# Adafruit_Feather_ESP32-S2.net
KiCad netlist of a schematic drawn in EAGLE
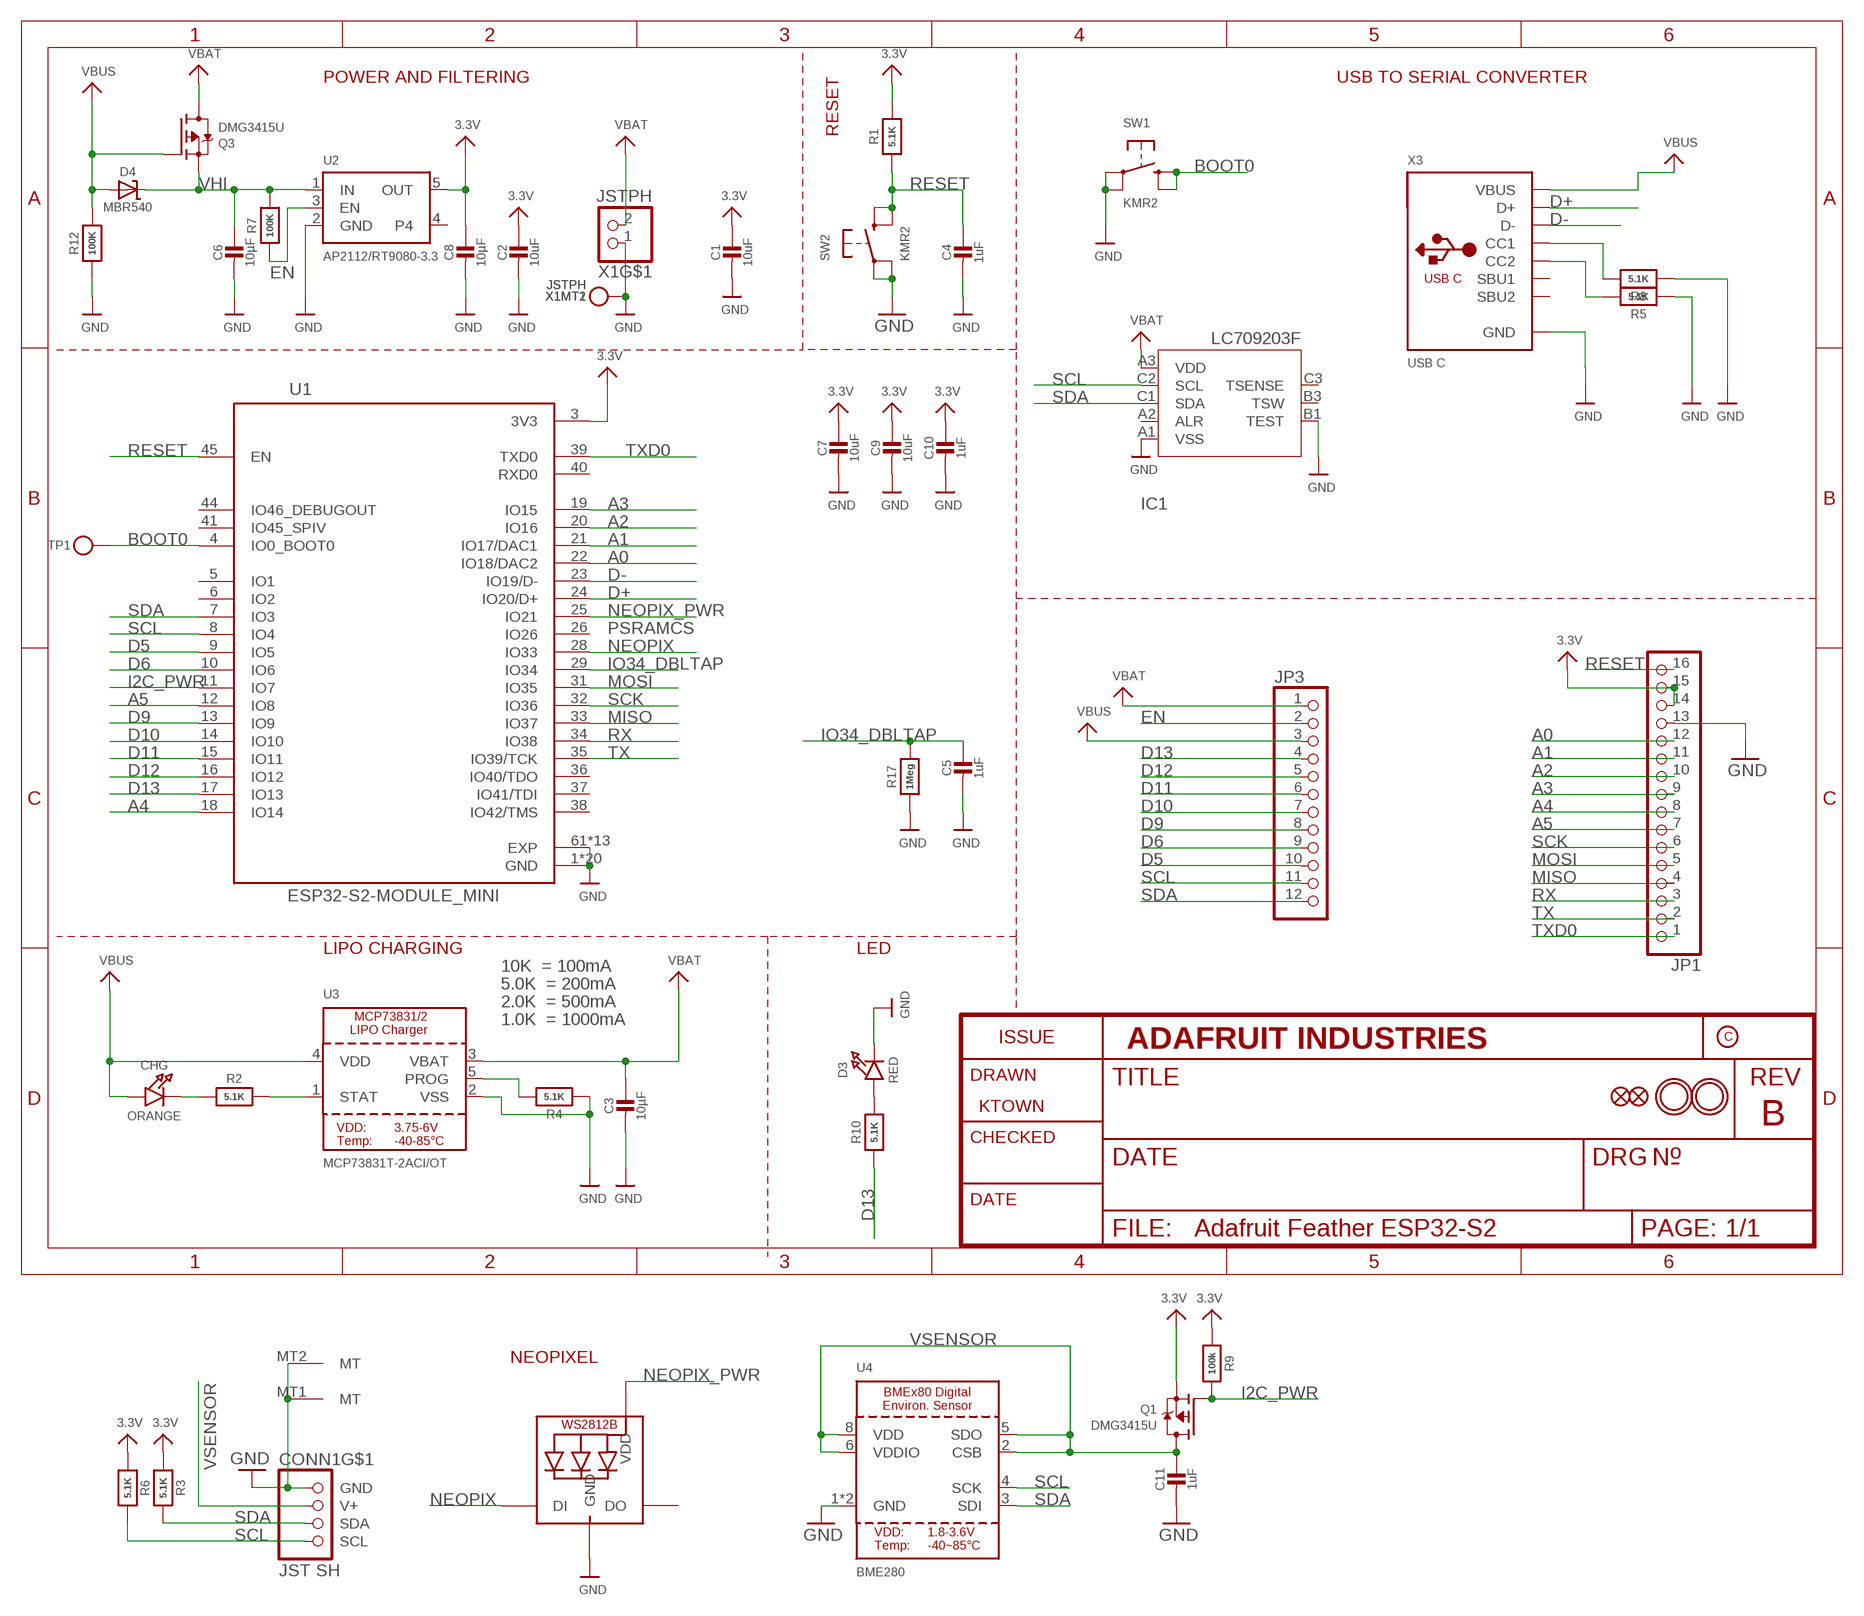
[diagram p0: schematic, sheet 1]

(export (version "E")
  (design (tool "Eeschema 10.0.6"))
  (components
    (comp (ref "C1")
      (value "10uF")
      (footprint "eagle-import:0805-NO")
      (libsource (lib "eagle-import") (part "CAP_CERAMIC0805-NOOUTLINE"))
    )
    (comp (ref "C2")
      (value "10uF")
      (footprint "eagle-import:0805-NO")
      (libsource (lib "eagle-import") (part "CAP_CERAMIC0805-NOOUTLINE"))
    )
    (comp (ref "C3")
      (value "10µF")
      (footprint "eagle-import:0805-NO")
      (libsource (lib "eagle-import") (part "CAP_CERAMIC0805-NOOUTLINE"))
    )
    (comp (ref "C4")
      (value "1uF")
      (footprint "eagle-import:0603-NO")
      (libsource (lib "eagle-import") (part "CAP_CERAMIC0603_NO"))
    )
    (comp (ref "C5")
      (value "1uF")
      (footprint "eagle-import:0603-NO")
      (libsource (lib "eagle-import") (part "CAP_CERAMIC0603_NO"))
    )
    (comp (ref "C6")
      (value "10µF")
      (footprint "eagle-import:0805-NO")
      (libsource (lib "eagle-import") (part "CAP_CERAMIC0805-NOOUTLINE"))
    )
    (comp (ref "C7")
      (value "10uF")
      (footprint "eagle-import:0805-NO")
      (libsource (lib "eagle-import") (part "CAP_CERAMIC0805-NOOUTLINE"))
    )
    (comp (ref "C8")
      (value "10µF")
      (footprint "eagle-import:0805-NO")
      (fields (field (name "REV") "B"))
      (libsource (lib "eagle-import") (part "CAP_CERAMIC0805-NOOUTLINE"))
    )
    (comp (ref "C9")
      (value "10uF")
      (footprint "eagle-import:0805-NO")
      (libsource (lib "eagle-import") (part "CAP_CERAMIC0805-NOOUTLINE"))
    )
    (comp (ref "C10")
      (value "1uF")
      (footprint "eagle-import:0603-NO")
      (libsource (lib "eagle-import") (part "CAP_CERAMIC0603_NO"))
    )
    (comp (ref "C11")
      (value "1uF")
      (footprint "eagle-import:0603-NO")
      (libsource (lib "eagle-import") (part "CAP_CERAMIC0603_NO"))
    )
    (comp (ref "CHG")
      (value "ORANGE")
      (footprint "eagle-import:CHIPLED_0603_NOOUTLINE")
      (libsource (lib "eagle-import") (part "LED0603_NOOUTLINE"))
    )
    (comp (ref "CONN1")
      (value "JST SH")
      (footprint "eagle-import:JST_SH4_RA")
      (libsource (lib "eagle-import") (part "STEMMA_I2C_QTRA"))
    )
    (comp (ref "D3")
      (value "RED")
      (footprint "eagle-import:CHIPLED_0603_NOOUTLINE")
      (libsource (lib "eagle-import") (part "LED0603_NOOUTLINE"))
    )
    (comp (ref "D4")
      (value "MBR540")
      (footprint "eagle-import:SOD-123")
      (libsource (lib "eagle-import") (part "DIODE-SCHOTTKYSOD-123"))
    )
    (comp (ref "IC1")
      (value "LC709203F/MH")
      (footprint "eagle-import:WLCSP9")
      (libsource (lib "eagle-import") (part "LC709203F/MH"))
    )
    (comp (ref "JP1")
      (value "HEADER-1X16ROUND")
      (footprint "eagle-import:1X16_ROUND")
      (libsource (lib "eagle-import") (part "HEADER-1X16ROUND"))
    )
    (comp (ref "JP3")
      (value "HEADER-1X12")
      (footprint "eagle-import:1X12_ROUND")
      (libsource (lib "eagle-import") (part "HEADER-1X12"))
    )
    (comp (ref "LED1")
      (value "WS2812B_SK6805_1515")
      (footprint "eagle-import:SK6805_1515")
      (libsource (lib "eagle-import") (part "WS2812B_SK6805_1515"))
    )
    (comp (ref "Q1")
      (value "DMG3415U")
      (footprint "eagle-import:SOT23-R")
      (libsource (lib "eagle-import") (part "MOSFET-P"))
    )
    (comp (ref "Q3")
      (value "DMG3415U")
      (footprint "eagle-import:SOT23-R")
      (libsource (lib "eagle-import") (part "MOSFET-P"))
    )
    (comp (ref "R1")
      (value "5.1K")
      (footprint "eagle-import:0603-NO")
      (libsource (lib "eagle-import") (part "RESISTOR_0603_NOOUT"))
    )
    (comp (ref "R2")
      (value "5.1K")
      (footprint "eagle-import:0603-NO")
      (libsource (lib "eagle-import") (part "RESISTOR_0603_NOOUT"))
    )
    (comp (ref "R3")
      (value "5.1K")
      (footprint "eagle-import:0603-NO")
      (libsource (lib "eagle-import") (part "RESISTOR_0603_NOOUT"))
    )
    (comp (ref "R4")
      (value "5.1K")
      (footprint "eagle-import:0603-NO")
      (libsource (lib "eagle-import") (part "RESISTOR_0603_NOOUT"))
    )
    (comp (ref "R5")
      (value "5.1K")
      (footprint "eagle-import:0603-NO")
      (libsource (lib "eagle-import") (part "RESISTOR_0603_NOOUT"))
    )
    (comp (ref "R6")
      (value "5.1K")
      (footprint "eagle-import:0603-NO")
      (libsource (lib "eagle-import") (part "RESISTOR_0603_NOOUT"))
    )
    (comp (ref "R7")
      (value "100K")
      (footprint "eagle-import:0603-NO")
      (libsource (lib "eagle-import") (part "RESISTOR_0603_NOOUT"))
    )
    (comp (ref "R8")
      (value "5.1K")
      (footprint "eagle-import:0603-NO")
      (libsource (lib "eagle-import") (part "RESISTOR_0603_NOOUT"))
    )
    (comp (ref "R9")
      (value "100k")
      (footprint "eagle-import:0603-NO")
      (libsource (lib "eagle-import") (part "RESISTOR_0603_NOOUT"))
    )
    (comp (ref "R10")
      (value "5.1K")
      (footprint "eagle-import:0603-NO")
      (libsource (lib "eagle-import") (part "RESISTOR_0603_NOOUT"))
    )
    (comp (ref "R12")
      (value "100K")
      (footprint "eagle-import:0603-NO")
      (libsource (lib "eagle-import") (part "RESISTOR_0603_NOOUT"))
    )
    (comp (ref "R17")
      (value "1Meg")
      (footprint "eagle-import:0603-NO")
      (libsource (lib "eagle-import") (part "RESISTOR_0603_NOOUT"))
    )
    (comp (ref "SW1")
      (value "KMR2")
      (footprint "eagle-import:BTN_KMR2_4.6X2.8")
      (libsource (lib "eagle-import") (part "SWITCH_TACT_SMT4.6X2.8"))
    )
    (comp (ref "SW2")
      (value "KMR2")
      (footprint "eagle-import:BTN_KMR2_4.6X2.8")
      (libsource (lib "eagle-import") (part "SWITCH_TACT_SMT4.6X2.8"))
    )
    (comp (ref "TP1")
      (value "TESTPOINTROUND1.5MMNO")
      (footprint "eagle-import:TESTPOINT_ROUND_1.5MM_NO")
      (libsource (lib "eagle-import") (part "TESTPOINTROUND1.5MMNO"))
    )
    (comp (ref "U$31")
      (value "MOUNTINGHOLE2.5")
      (footprint "eagle-import:MOUNTINGHOLE_2.5_PLATED")
      (libsource (lib "eagle-import") (part "MOUNTINGHOLE2.5"))
    )
    (comp (ref "U$32")
      (value "MOUNTINGHOLE2.5")
      (footprint "eagle-import:MOUNTINGHOLE_2.5_PLATED")
      (libsource (lib "eagle-import") (part "MOUNTINGHOLE2.5"))
    )
    (comp (ref "U$34")
      (value "FIDUCIAL_1MM")
      (footprint "eagle-import:FIDUCIAL_1MM")
      (libsource (lib "eagle-import") (part "FIDUCIAL_1MM"))
    )
    (comp (ref "U$35")
      (value "FIDUCIAL_1MM")
      (footprint "eagle-import:FIDUCIAL_1MM")
      (libsource (lib "eagle-import") (part "FIDUCIAL_1MM"))
    )
    (comp (ref "U1")
      (value "ESP32-S2-MODULE_MINI")
      (footprint "eagle-import:QFN60_ESP32-S2-MINI-1_EXP")
      (libsource (lib "eagle-import") (part "ESP32-S2-MODULE_MINI"))
    )
    (comp (ref "U2")
      (value "AP2112/RT9080-3.3")
      (footprint "eagle-import:SOT23-5")
      (libsource (lib "eagle-import") (part "VREG_SOT23-5"))
    )
    (comp (ref "U3")
      (value "MCP73831T-2ACI/OT")
      (footprint "eagle-import:SOT23-5")
      (libsource (lib "eagle-import") (part "MCP73831/2"))
    )
    (comp (ref "U4")
      (value "BME280")
      (footprint "eagle-import:BME280")
      (libsource (lib "eagle-import") (part "BME280"))
    )
    (comp (ref "X1")
      (value "JSTPH")
      (footprint "eagle-import:JSTPH2_BATT")
      (libsource (lib "eagle-import") (part "CON_JST_PH_2PIN_MT_BATT"))
    )
    (comp (ref "X3")
      (value "USB C")
      (footprint "eagle-import:USB_C_CUSB31-CFM2AX-01-X")
      (libsource (lib "eagle-import") (part "USB_C"))
    )
  )
  (nets
    (net (code "1") (name "/A0") (class "Default")
      (node (ref "JP1") (pin "12") (pinfunction "12_12") (pintype "passive"))
      (node (ref "U1") (pin "22") (pinfunction "IO18/DAC2_22") (pintype "bidirectional"))
    )
    (net (code "2") (name "/A1") (class "Default")
      (node (ref "JP1") (pin "11") (pinfunction "11_11") (pintype "passive"))
      (node (ref "U1") (pin "21") (pinfunction "IO17/DAC1_21") (pintype "bidirectional"))
    )
    (net (code "3") (name "/A2") (class "Default")
      (node (ref "JP1") (pin "10") (pinfunction "10_10") (pintype "passive"))
      (node (ref "U1") (pin "20") (pinfunction "IO16_20") (pintype "bidirectional"))
    )
    (net (code "4") (name "/A3") (class "Default")
      (node (ref "JP1") (pin "9") (pinfunction "9_9") (pintype "passive"))
      (node (ref "U1") (pin "19") (pinfunction "IO15_19") (pintype "bidirectional"))
    )
    (net (code "5") (name "/A4") (class "Default")
      (node (ref "JP1") (pin "8") (pinfunction "8_8") (pintype "passive"))
      (node (ref "U1") (pin "18") (pinfunction "IO14_18") (pintype "bidirectional"))
    )
    (net (code "6") (name "/A5") (class "Default")
      (node (ref "JP1") (pin "7") (pinfunction "7_7") (pintype "passive"))
      (node (ref "U1") (pin "12") (pinfunction "IO8_12") (pintype "bidirectional"))
    )
    (net (code "7") (name "/BOOT0") (class "Default")
      (node (ref "SW1") (pin "B") (pinfunction "S_B") (pintype "passive"))
      (node (ref "SW1") (pin "B'") (pinfunction "S1_B'") (pintype "passive"))
      (node (ref "TP1") (pin "P$1") (pinfunction "P$1_P$1") (pintype "bidirectional"))
      (node (ref "U1") (pin "4") (pinfunction "IO0_BOOT0_4") (pintype "bidirectional"))
    )
    (net (code "8") (name "/D+") (class "Default")
      (node (ref "U1") (pin "24") (pinfunction "IO20/D+_24") (pintype "bidirectional"))
      (node (ref "X3") (pin "A6") (pinfunction "D+_A6") (pintype "bidirectional"))
      (node (ref "X3") (pin "B6") (pinfunction "D+_B6") (pintype "bidirectional"))
    )
    (net (code "9") (name "/D-") (class "Default")
      (node (ref "U1") (pin "23") (pinfunction "IO19/D-_23") (pintype "bidirectional"))
      (node (ref "X3") (pin "A7") (pinfunction "D-_A7") (pintype "bidirectional"))
      (node (ref "X3") (pin "B7") (pinfunction "D-_B7") (pintype "bidirectional"))
    )
    (net (code "10") (name "/D5") (class "Default")
      (node (ref "JP3") (pin "10") (pinfunction "10_10") (pintype "passive"))
      (node (ref "U1") (pin "9") (pinfunction "IO5_9") (pintype "bidirectional"))
    )
    (net (code "11") (name "/D6") (class "Default")
      (node (ref "JP3") (pin "9") (pinfunction "9_9") (pintype "passive"))
      (node (ref "U1") (pin "10") (pinfunction "IO6_10") (pintype "bidirectional"))
    )
    (net (code "12") (name "/D9") (class "Default")
      (node (ref "JP3") (pin "8") (pinfunction "8_8") (pintype "passive"))
      (node (ref "U1") (pin "13") (pinfunction "IO9_13") (pintype "bidirectional"))
    )
    (net (code "13") (name "/D10") (class "Default")
      (node (ref "JP3") (pin "7") (pinfunction "7_7") (pintype "passive"))
      (node (ref "U1") (pin "14") (pinfunction "IO10_14") (pintype "bidirectional"))
    )
    (net (code "14") (name "/D11") (class "Default")
      (node (ref "JP3") (pin "6") (pinfunction "6_6") (pintype "passive"))
      (node (ref "U1") (pin "15") (pinfunction "IO11_15") (pintype "bidirectional"))
    )
    (net (code "15") (name "/D12") (class "Default")
      (node (ref "JP3") (pin "5") (pinfunction "5_5") (pintype "passive"))
      (node (ref "U1") (pin "16") (pinfunction "IO12_16") (pintype "bidirectional"))
    )
    (net (code "16") (name "/D13") (class "Default")
      (node (ref "JP3") (pin "4") (pinfunction "4_4") (pintype "passive"))
      (node (ref "R10") (pin "1") (pinfunction "1_1") (pintype "passive"))
      (node (ref "U1") (pin "17") (pinfunction "IO13_17") (pintype "bidirectional"))
    )
    (net (code "17") (name "/EN") (class "Default")
      (node (ref "JP3") (pin "2") (pinfunction "2_2") (pintype "passive"))
      (node (ref "R7") (pin "1") (pinfunction "1_1") (pintype "passive"))
      (node (ref "U2") (pin "3") (pinfunction "EN_3") (pintype "input"))
    )
    (net (code "18") (name "/I2C_PWR") (class "Default")
      (node (ref "Q1") (pin "1") (pinfunction "G_1") (pintype "passive"))
      (node (ref "R9") (pin "1") (pinfunction "1_1") (pintype "passive"))
      (node (ref "U1") (pin "11") (pinfunction "IO7_11") (pintype "bidirectional"))
    )
    (net (code "19") (name "/IO34_DBLTAP") (class "Default")
      (node (ref "C5") (pin "1") (pinfunction "1_1") (pintype "passive"))
      (node (ref "R17") (pin "2") (pinfunction "2_2") (pintype "passive"))
      (node (ref "U1") (pin "29") (pinfunction "IO34_29") (pintype "input"))
    )
    (net (code "20") (name "/MISO") (class "Default")
      (node (ref "JP1") (pin "4") (pinfunction "4_4") (pintype "passive"))
      (node (ref "U1") (pin "33") (pinfunction "IO37_33") (pintype "bidirectional"))
    )
    (net (code "21") (name "/MOSI") (class "Default")
      (node (ref "JP1") (pin "5") (pinfunction "5_5") (pintype "passive"))
      (node (ref "U1") (pin "31") (pinfunction "IO35_31") (pintype "input"))
    )
    (net (code "22") (name "/NEOPIX") (class "Default")
      (node (ref "LED1") (pin "1") (pinfunction "DI_1") (pintype "input"))
      (node (ref "U1") (pin "28") (pinfunction "IO33_28") (pintype "bidirectional"))
    )
    (net (code "23") (name "/NEOPIX_PWR") (class "Default")
      (node (ref "LED1") (pin "2") (pinfunction "VDD_2") (pintype "power_in"))
      (node (ref "U1") (pin "25") (pinfunction "IO21_25") (pintype "bidirectional"))
    )
    (net (code "24") (name "/RESET") (class "Default")
      (node (ref "C4") (pin "1") (pinfunction "1_1") (pintype "passive"))
      (node (ref "JP1") (pin "16") (pinfunction "16_16") (pintype "passive"))
      (node (ref "R1") (pin "1") (pinfunction "1_1") (pintype "passive"))
      (node (ref "SW2") (pin "B") (pinfunction "S_B") (pintype "passive"))
      (node (ref "SW2") (pin "B'") (pinfunction "S1_B'") (pintype "passive"))
      (node (ref "U1") (pin "45") (pinfunction "EN_45") (pintype "input"))
    )
    (net (code "25") (name "/RX") (class "Default")
      (node (ref "JP1") (pin "3") (pinfunction "3_3") (pintype "passive"))
      (node (ref "U1") (pin "34") (pinfunction "IO38_34") (pintype "bidirectional"))
    )
    (net (code "26") (name "/SCK") (class "Default")
      (node (ref "JP1") (pin "6") (pinfunction "6_6") (pintype "passive"))
      (node (ref "U1") (pin "32") (pinfunction "IO36_32") (pintype "bidirectional"))
    )
    (net (code "27") (name "/SCL") (class "Default")
      (node (ref "CONN1") (pin "4") (pinfunction "SCL_4") (pintype "passive"))
      (node (ref "IC1") (pin "C2") (pinfunction "SCL_C2") (pintype "bidirectional"))
      (node (ref "JP3") (pin "11") (pinfunction "11_11") (pintype "passive"))
      (node (ref "R6") (pin "2") (pinfunction "2_2") (pintype "passive"))
      (node (ref "U1") (pin "8") (pinfunction "IO4_8") (pintype "bidirectional"))
      (node (ref "U4") (pin "4") (pinfunction "SCK_4") (pintype "input"))
    )
    (net (code "28") (name "/SDA") (class "Default")
      (node (ref "CONN1") (pin "3") (pinfunction "SDA_3") (pintype "passive"))
      (node (ref "IC1") (pin "C1") (pinfunction "SDA_C1") (pintype "bidirectional"))
      (node (ref "JP3") (pin "12") (pinfunction "12_12") (pintype "passive"))
      (node (ref "R3") (pin "2") (pinfunction "2_2") (pintype "passive"))
      (node (ref "U1") (pin "7") (pinfunction "IO3_7") (pintype "bidirectional"))
      (node (ref "U4") (pin "3") (pinfunction "SDI_3") (pintype "input"))
    )
    (net (code "29") (name "/TX") (class "Default")
      (node (ref "JP1") (pin "2") (pinfunction "2_2") (pintype "passive"))
      (node (ref "U1") (pin "35") (pinfunction "IO39/TCK_35") (pintype "bidirectional"))
    )
    (net (code "30") (name "/TXD0") (class "Default")
      (node (ref "JP1") (pin "1") (pinfunction "1_1") (pintype "passive"))
      (node (ref "U1") (pin "39") (pinfunction "TXD0_39") (pintype "bidirectional"))
    )
    (net (code "31") (name "/VHI") (class "Default")
      (node (ref "C6") (pin "1") (pinfunction "1_1") (pintype "passive"))
      (node (ref "D4") (pin "C") (pinfunction "C_C") (pintype "passive"))
      (node (ref "Q3") (pin "2") (pinfunction "S_2") (pintype "passive"))
      (node (ref "R7") (pin "2") (pinfunction "2_2") (pintype "passive"))
      (node (ref "U2") (pin "1") (pinfunction "IN_1") (pintype "power_in"))
    )
    (net (code "32") (name "/VSENSOR") (class "Default")
      (node (ref "C11") (pin "1") (pinfunction "1_1") (pintype "passive"))
      (node (ref "CONN1") (pin "2") (pinfunction "V+_2") (pintype "passive"))
      (node (ref "Q1") (pin "3") (pinfunction "D_3") (pintype "passive"))
      (node (ref "U4") (pin "2") (pinfunction "CSB_2") (pintype "input"))
      (node (ref "U4") (pin "5") (pinfunction "SDO_5") (pintype "output"))
      (node (ref "U4") (pin "6") (pinfunction "VDDIO_6") (pintype "power_in"))
      (node (ref "U4") (pin "8") (pinfunction "VDD_8") (pintype "power_in"))
    )
    (net (code "33") (name "3.3V") (class "Default")
      (node (ref "C1") (pin "1") (pinfunction "1_1") (pintype "passive"))
      (node (ref "C10") (pin "1") (pinfunction "1_1") (pintype "passive"))
      (node (ref "C2") (pin "1") (pinfunction "1_1") (pintype "passive"))
      (node (ref "C7") (pin "1") (pinfunction "1_1") (pintype "passive"))
      (node (ref "C8") (pin "1") (pinfunction "1_1") (pintype "passive"))
      (node (ref "C9") (pin "1") (pinfunction "1_1") (pintype "passive"))
      (node (ref "JP1") (pin "14") (pinfunction "14_14") (pintype "passive"))
      (node (ref "JP1") (pin "15") (pinfunction "15_15") (pintype "passive"))
      (node (ref "Q1") (pin "2") (pinfunction "S_2") (pintype "passive"))
      (node (ref "R1") (pin "2") (pinfunction "2_2") (pintype "passive"))
      (node (ref "R3") (pin "1") (pinfunction "1_1") (pintype "passive"))
      (node (ref "R6") (pin "1") (pinfunction "1_1") (pintype "passive"))
      (node (ref "R9") (pin "2") (pinfunction "2_2") (pintype "passive"))
      (node (ref "U1") (pin "3") (pinfunction "3V3_3") (pintype "power_in"))
      (node (ref "U2") (pin "5") (pinfunction "OUT_5") (pintype "power_in"))
    )
    (net (code "34") (name "GND") (class "Default")
      (node (ref "C1") (pin "2") (pinfunction "2_2") (pintype "passive"))
      (node (ref "C10") (pin "2") (pinfunction "2_2") (pintype "passive"))
      (node (ref "C11") (pin "2") (pinfunction "2_2") (pintype "passive"))
      (node (ref "C2") (pin "2") (pinfunction "2_2") (pintype "passive"))
      (node (ref "C3") (pin "2") (pinfunction "2_2") (pintype "passive"))
      (node (ref "C4") (pin "2") (pinfunction "2_2") (pintype "passive"))
      (node (ref "C5") (pin "2") (pinfunction "2_2") (pintype "passive"))
      (node (ref "C6") (pin "2") (pinfunction "2_2") (pintype "passive"))
      (node (ref "C7") (pin "2") (pinfunction "2_2") (pintype "passive"))
      (node (ref "C8") (pin "2") (pinfunction "2_2") (pintype "passive"))
      (node (ref "C9") (pin "2") (pinfunction "2_2") (pintype "passive"))
      (node (ref "CONN1") (pin "1") (pinfunction "GND_1") (pintype "passive"))
      (node (ref "CONN1") (pin "MT1") (pinfunction "MT_MT1") (pintype "bidirectional"))
      (node (ref "CONN1") (pin "MT2") (pinfunction "MT_MT2") (pintype "bidirectional"))
      (node (ref "D3") (pin "C") (pinfunction "C_C") (pintype "passive"))
      (node (ref "IC1") (pin "A1") (pinfunction "VSS_A1") (pintype "power_in"))
      (node (ref "IC1") (pin "B1") (pinfunction "TEST_B1") (pintype "input"))
      (node (ref "JP1") (pin "13") (pinfunction "13_13") (pintype "passive"))
      (node (ref "LED1") (pin "4") (pinfunction "GND_4") (pintype "power_in"))
      (node (ref "R12") (pin "1") (pinfunction "1_1") (pintype "passive"))
      (node (ref "R17") (pin "1") (pinfunction "1_1") (pintype "passive"))
      (node (ref "R4") (pin "1") (pinfunction "1_1") (pintype "passive"))
      (node (ref "R5") (pin "1") (pinfunction "1_1") (pintype "passive"))
      (node (ref "R8") (pin "1") (pinfunction "1_1") (pintype "passive"))
      (node (ref "SW1") (pin "A") (pinfunction "P_A") (pintype "passive"))
      (node (ref "SW1") (pin "A'") (pinfunction "P1_A'") (pintype "passive"))
      (node (ref "SW2") (pin "A") (pinfunction "P_A") (pintype "passive"))
      (node (ref "SW2") (pin "A'") (pinfunction "P1_A'") (pintype "passive"))
      (node (ref "U1") (pin "1") (pinfunction "GND_1") (pintype "power_in"))
      (node (ref "U1") (pin "2") (pinfunction "GND_2") (pintype "power_in"))
      (node (ref "U1") (pin "30") (pinfunction "GND_30") (pintype "power_in"))
      (node (ref "U1") (pin "42") (pinfunction "GND_42") (pintype "power_in"))
      (node (ref "U1") (pin "43") (pinfunction "GND_43") (pintype "power_in"))
      (node (ref "U1") (pin "46") (pinfunction "GND_46") (pintype "power_in"))
      (node (ref "U1") (pin "47") (pinfunction "GND_47") (pintype "power_in"))
      (node (ref "U1") (pin "48") (pinfunction "GND_48") (pintype "power_in"))
      (node (ref "U1") (pin "49") (pinfunction "GND_49") (pintype "power_in"))
      (node (ref "U1") (pin "50") (pinfunction "GND_50") (pintype "power_in"))
      (node (ref "U1") (pin "51") (pinfunction "GND_51") (pintype "power_in"))
      (node (ref "U1") (pin "52") (pinfunction "GND_52") (pintype "power_in"))
      (node (ref "U1") (pin "53") (pinfunction "GND_53") (pintype "power_in"))
      (node (ref "U1") (pin "54") (pinfunction "GND_54") (pintype "power_in"))
      (node (ref "U1") (pin "55") (pinfunction "GND_55") (pintype "power_in"))
      (node (ref "U1") (pin "56") (pinfunction "GND_56") (pintype "power_in"))
      (node (ref "U1") (pin "57") (pinfunction "GND_57") (pintype "power_in"))
      (node (ref "U1") (pin "58") (pinfunction "GND_58") (pintype "power_in"))
      (node (ref "U1") (pin "59") (pinfunction "GND_59") (pintype "power_in"))
      (node (ref "U1") (pin "60") (pinfunction "GND_60") (pintype "power_in"))
      (node (ref "U1") (pin "61") (pinfunction "EXP_61") (pintype "power_in"))
      (node (ref "U1") (pin "62") (pinfunction "EXP_62") (pintype "power_in"))
      (node (ref "U1") (pin "63") (pinfunction "EXP_63") (pintype "power_in"))
      (node (ref "U1") (pin "64") (pinfunction "EXP_64") (pintype "power_in"))
      (node (ref "U1") (pin "65") (pinfunction "EXP_65") (pintype "power_in"))
      (node (ref "U1") (pin "66") (pinfunction "EXP_66") (pintype "power_in"))
      (node (ref "U1") (pin "67") (pinfunction "EXP_67") (pintype "power_in"))
      (node (ref "U1") (pin "68") (pinfunction "EXP_68") (pintype "power_in"))
      (node (ref "U1") (pin "69") (pinfunction "EXP_69") (pintype "power_in"))
      (node (ref "U1") (pin "70") (pinfunction "EXP_70") (pintype "power_in"))
      (node (ref "U1") (pin "71") (pinfunction "EXP_71") (pintype "power_in"))
      (node (ref "U1") (pin "72") (pinfunction "EXP_72") (pintype "power_in"))
      (node (ref "U1") (pin "73") (pinfunction "EXP_73") (pintype "power_in"))
      (node (ref "U2") (pin "2") (pinfunction "GND_2") (pintype "power_in"))
      (node (ref "U3") (pin "2") (pinfunction "VSS_2") (pintype "power_in"))
      (node (ref "U4") (pin "1") (pinfunction "GND_1") (pintype "power_in"))
      (node (ref "U4") (pin "7") (pinfunction "GND_7") (pintype "power_in"))
      (node (ref "X1") (pin "1") (pinfunction "1_1") (pintype "passive"))
      (node (ref "X1") (pin "NC1") (pinfunction "P$1_NC1") (pintype "bidirectional"))
      (node (ref "X1") (pin "NC2") (pinfunction "P$1_NC2") (pintype "bidirectional"))
      (node (ref "X3") (pin "A1B12") (pinfunction "GND_A1B12") (pintype "power_in"))
      (node (ref "X3") (pin "B1A12") (pinfunction "GND_B1A12") (pintype "power_in"))
    )
    (net (code "35") (name "Net-(CHG-PadC)") (class "Default")
      (node (ref "CHG") (pin "C") (pinfunction "C_C") (pintype "passive"))
      (node (ref "R2") (pin "1") (pinfunction "1_1") (pintype "passive"))
    )
    (net (code "36") (name "Net-(D3-PadA)") (class "Default")
      (node (ref "D3") (pin "A") (pinfunction "A_A") (pintype "passive"))
      (node (ref "R10") (pin "2") (pinfunction "2_2") (pintype "passive"))
    )
    (net (code "37") (name "Net-(U3-PROG)") (class "Default")
      (node (ref "R4") (pin "2") (pinfunction "2_2") (pintype "passive"))
      (node (ref "U3") (pin "5") (pinfunction "PROG_5") (pintype "input"))
    )
    (net (code "38") (name "Net-(U3-STAT)") (class "Default")
      (node (ref "R2") (pin "2") (pinfunction "2_2") (pintype "passive"))
      (node (ref "U3") (pin "1") (pinfunction "STAT_1") (pintype "output"))
    )
    (net (code "39") (name "Net-(X3-CC1)") (class "Default")
      (node (ref "R8") (pin "2") (pinfunction "2_2") (pintype "passive"))
      (node (ref "X3") (pin "A5") (pinfunction "CC1_A5") (pintype "bidirectional"))
    )
    (net (code "40") (name "Net-(X3-CC2)") (class "Default")
      (node (ref "R5") (pin "2") (pinfunction "2_2") (pintype "passive"))
      (node (ref "X3") (pin "B5") (pinfunction "CC2_B5") (pintype "bidirectional"))
    )
    (net (code "41") (name "VBAT") (class "Default")
      (node (ref "C3") (pin "1") (pinfunction "1_1") (pintype "passive"))
      (node (ref "IC1") (pin "A3") (pinfunction "VDD_A3") (pintype "power_in"))
      (node (ref "JP3") (pin "1") (pinfunction "1_1") (pintype "passive"))
      (node (ref "Q3") (pin "3") (pinfunction "D_3") (pintype "passive"))
      (node (ref "U3") (pin "3") (pinfunction "VBAT_3") (pintype "power_in"))
      (node (ref "X1") (pin "2") (pinfunction "2_2") (pintype "passive"))
    )
    (net (code "42") (name "VBUS") (class "Default")
      (node (ref "CHG") (pin "A") (pinfunction "A_A") (pintype "passive"))
      (node (ref "D4") (pin "A") (pinfunction "A_A") (pintype "passive"))
      (node (ref "JP3") (pin "3") (pinfunction "3_3") (pintype "passive"))
      (node (ref "Q3") (pin "1") (pinfunction "G_1") (pintype "passive"))
      (node (ref "R12") (pin "2") (pinfunction "2_2") (pintype "passive"))
      (node (ref "U3") (pin "4") (pinfunction "VDD_4") (pintype "power_in"))
      (node (ref "X3") (pin "A4B9") (pinfunction "VBUS_A4B9") (pintype "power_in"))
      (node (ref "X3") (pin "B4A9") (pinfunction "VBUS_B4A9") (pintype "power_in"))
    )
    (net (code "43") (name "unconnected-(IC1-ALR-PadA2)") (class "Default")
      (node (ref "IC1") (pin "A2") (pinfunction "ALR_A2") (pintype "output"))
    )
    (net (code "44") (name "unconnected-(IC1-TSENSE-PadC3)") (class "Default")
      (node (ref "IC1") (pin "C3") (pinfunction "TSENSE_C3") (pintype "passive"))
    )
    (net (code "45") (name "unconnected-(IC1-TSW-PadB3)") (class "Default")
      (node (ref "IC1") (pin "B3") (pinfunction "TSW_B3") (pintype "output"))
    )
    (net (code "46") (name "unconnected-(LED1-DO-Pad3)") (class "Default")
      (node (ref "LED1") (pin "3") (pinfunction "DO_3") (pintype "output"))
    )
    (net (code "47") (name "unconnected-(U1-IO1-Pad5)") (class "Default")
      (node (ref "U1") (pin "5") (pinfunction "IO1_5") (pintype "bidirectional"))
    )
    (net (code "48") (name "unconnected-(U1-IO2-Pad6)") (class "Default")
      (node (ref "U1") (pin "6") (pinfunction "IO2_6") (pintype "bidirectional"))
    )
    (net (code "49") (name "unconnected-(U1-IO26-Pad26)") (class "Default")
      (node (ref "U1") (pin "26") (pinfunction "IO26_26") (pintype "bidirectional"))
    )
    (net (code "50") (name "unconnected-(U1-IO40{slash}TDO-Pad36)") (class "Default")
      (node (ref "U1") (pin "36") (pinfunction "IO40/TDO_36") (pintype "bidirectional"))
    )
    (net (code "51") (name "unconnected-(U1-IO41{slash}TDI-Pad37)") (class "Default")
      (node (ref "U1") (pin "37") (pinfunction "IO41/TDI_37") (pintype "bidirectional"))
    )
    (net (code "52") (name "unconnected-(U1-IO42{slash}TMS-Pad38)") (class "Default")
      (node (ref "U1") (pin "38") (pinfunction "IO42/TMS_38") (pintype "bidirectional"))
    )
    (net (code "53") (name "unconnected-(U1-IO45_SPIV-Pad41)") (class "Default")
      (node (ref "U1") (pin "41") (pinfunction "IO45_SPIV_41") (pintype "bidirectional"))
    )
    (net (code "54") (name "unconnected-(U1-IO46_DEBUGOUT-Pad44)") (class "Default")
      (node (ref "U1") (pin "44") (pinfunction "IO46_DEBUGOUT_44") (pintype "input"))
    )
    (net (code "55") (name "unconnected-(U1-RXD0-Pad40)") (class "Default")
      (node (ref "U1") (pin "40") (pinfunction "RXD0_40") (pintype "bidirectional"))
    )
    (net (code "56") (name "unconnected-(U2-P4-Pad4)") (class "Default")
      (node (ref "U2") (pin "4") (pinfunction "P4_4") (pintype "bidirectional"))
    )
    (net (code "57") (name "unconnected-(X3-SBU1-PadA8)") (class "Default")
      (node (ref "X3") (pin "A8") (pinfunction "SBU1_A8") (pintype "bidirectional"))
    )
    (net (code "58") (name "unconnected-(X3-SBU2-PadB8)") (class "Default")
      (node (ref "X3") (pin "B8") (pinfunction "SBU2_B8") (pintype "bidirectional"))
    )
  )
)
